# tick-shield-mk-1.net
KiCad netlist of a schematic drawn in EAGLE
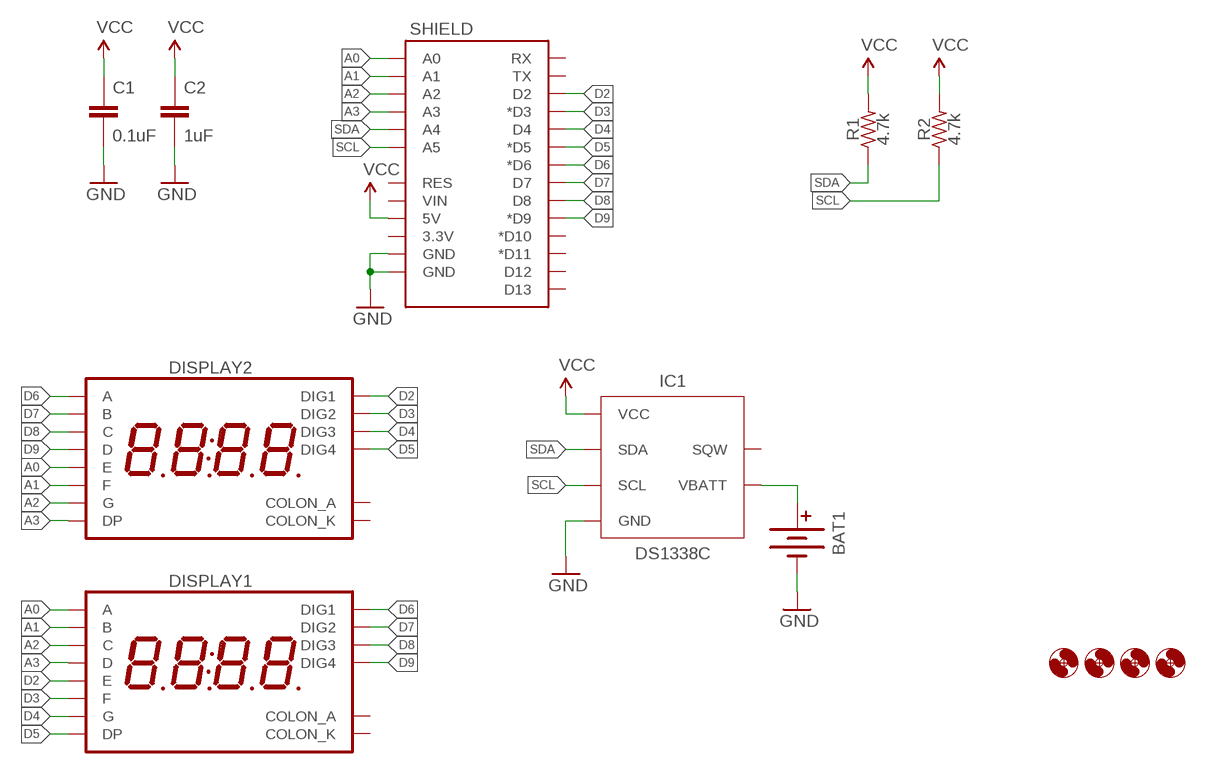
[diagram p0: schematic, sheet 1]

(export (version "E")
  (design (tool "Eeschema 10.0.6"))
  (components
    (comp (ref "BAT1")
      (value "BATTERY12MM")
      (footprint "eagle-import:BATTCON_12MM")
      (libsource (lib "eagle-import") (part "BATTERY12MM"))
    )
    (comp (ref "C1")
      (value "0.1uF")
      (footprint "eagle-import:C0603")
      (libsource (lib "eagle-import") (part "CAPACITOR-CERAMICC0603"))
    )
    (comp (ref "C2")
      (value "1uF")
      (footprint "eagle-import:C0805")
      (libsource (lib "eagle-import") (part "CAPACITOR-CERAMICC0805"))
    )
    (comp (ref "DISPLAY1")
      (value "7SEG_4DIGIT_COLON14.2MM-CC")
      (footprint "eagle-import:7SEG_4DIG_0.56IN_14MM_ADAFRUIT")
      (libsource (lib "eagle-import") (part "7SEG_4DIGIT_COLON14.2MM-CC"))
    )
    (comp (ref "DISPLAY2")
      (value "7SEG_4DIGIT_COLON14.2MM-CC")
      (footprint "eagle-import:7SEG_4DIG_0.56IN_14MM_ADAFRUIT")
      (libsource (lib "eagle-import") (part "7SEG_4DIGIT_COLON14.2MM-CC"))
    )
    (comp (ref "H1")
      (value "HOLE#2")
      (footprint "eagle-import:HOLE-#2")
      (libsource (lib "eagle-import") (part "HOLE#2"))
    )
    (comp (ref "H2")
      (value "HOLE#2")
      (footprint "eagle-import:HOLE-#2")
      (libsource (lib "eagle-import") (part "HOLE#2"))
    )
    (comp (ref "H3")
      (value "HOLE#2")
      (footprint "eagle-import:HOLE-#2")
      (libsource (lib "eagle-import") (part "HOLE#2"))
    )
    (comp (ref "H4")
      (value "HOLE#2")
      (footprint "eagle-import:HOLE-#2")
      (libsource (lib "eagle-import") (part "HOLE#2"))
    )
    (comp (ref "IC1")
      (value "DS1338C")
      (footprint "eagle-import:SO16W")
      (libsource (lib "eagle-import") (part "DS1338CSOIC16W"))
    )
    (comp (ref "R1")
      (value "4.7k")
      (footprint "eagle-import:R0603")
      (libsource (lib "eagle-import") (part "RESISTORR0603"))
    )
    (comp (ref "R2")
      (value "4.7k")
      (footprint "eagle-import:R0603")
      (libsource (lib "eagle-import") (part "RESISTORR0603"))
    )
    (comp (ref "SHIELD")
      (value "ARDUINO_SHIELD_SMALLER")
      (footprint "eagle-import:ARDUINO_SHIELD_NOOUTLINE_INSIDE_SMALLER")
      (libsource (lib "eagle-import") (part "ARDUINO_SHIELD_SMALLER"))
    )
  )
  (nets
    (net (code "1") (name "A0") (class "Default")
      (node (ref "DISPLAY1") (pin "P$13") (pinfunction "A_P$13") (pintype "passive"))
      (node (ref "DISPLAY2") (pin "P$1") (pinfunction "E_P$1") (pintype "passive"))
      (node (ref "SHIELD") (pin "A0") (pinfunction "A0_A0") (pintype "bidirectional"))
    )
    (net (code "2") (name "A1") (class "Default")
      (node (ref "DISPLAY1") (pin "P$9") (pinfunction "B_P$9") (pintype "passive"))
      (node (ref "DISPLAY2") (pin "P$12") (pinfunction "F_P$12") (pintype "passive"))
      (node (ref "SHIELD") (pin "A1") (pinfunction "A1_A1") (pintype "bidirectional"))
    )
    (net (code "3") (name "A2") (class "Default")
      (node (ref "DISPLAY1") (pin "P$4") (pinfunction "C_P$4") (pintype "passive"))
      (node (ref "DISPLAY2") (pin "P$5") (pinfunction "G_P$5") (pintype "passive"))
      (node (ref "SHIELD") (pin "A2") (pinfunction "A2_A2") (pintype "bidirectional"))
    )
    (net (code "4") (name "A3") (class "Default")
      (node (ref "DISPLAY1") (pin "P$2") (pinfunction "D_P$2") (pintype "passive"))
      (node (ref "DISPLAY2") (pin "P$3") (pinfunction "DP_P$3") (pintype "passive"))
      (node (ref "SHIELD") (pin "A3") (pinfunction "A3_A3") (pintype "bidirectional"))
    )
    (net (code "5") (name "D2") (class "Default")
      (node (ref "DISPLAY1") (pin "P$1") (pinfunction "E_P$1") (pintype "passive"))
      (node (ref "DISPLAY2") (pin "P$14") (pinfunction "DIG1_P$14") (pintype "passive"))
      (node (ref "SHIELD") (pin "D2") (pinfunction "D2_D2") (pintype "bidirectional"))
    )
    (net (code "6") (name "D3") (class "Default")
      (node (ref "DISPLAY1") (pin "P$12") (pinfunction "F_P$12") (pintype "passive"))
      (node (ref "DISPLAY2") (pin "P$11") (pinfunction "DIG2_P$11") (pintype "passive"))
      (node (ref "SHIELD") (pin "D3") (pinfunction "*D3_D3") (pintype "bidirectional"))
    )
    (net (code "7") (name "D4") (class "Default")
      (node (ref "DISPLAY1") (pin "P$5") (pinfunction "G_P$5") (pintype "passive"))
      (node (ref "DISPLAY2") (pin "P$10") (pinfunction "DIG3_P$10") (pintype "passive"))
      (node (ref "SHIELD") (pin "D4") (pinfunction "D4_D4") (pintype "bidirectional"))
    )
    (net (code "8") (name "D5") (class "Default")
      (node (ref "DISPLAY1") (pin "P$3") (pinfunction "DP_P$3") (pintype "passive"))
      (node (ref "DISPLAY2") (pin "P$6") (pinfunction "DIG4_P$6") (pintype "passive"))
      (node (ref "SHIELD") (pin "D5") (pinfunction "*D5_D5") (pintype "bidirectional"))
    )
    (net (code "9") (name "D6") (class "Default")
      (node (ref "DISPLAY1") (pin "P$14") (pinfunction "DIG1_P$14") (pintype "passive"))
      (node (ref "DISPLAY2") (pin "P$13") (pinfunction "A_P$13") (pintype "passive"))
      (node (ref "SHIELD") (pin "D6") (pinfunction "*D6_D6") (pintype "bidirectional"))
    )
    (net (code "10") (name "D7") (class "Default")
      (node (ref "DISPLAY1") (pin "P$11") (pinfunction "DIG2_P$11") (pintype "passive"))
      (node (ref "DISPLAY2") (pin "P$9") (pinfunction "B_P$9") (pintype "passive"))
      (node (ref "SHIELD") (pin "D7") (pinfunction "D7_D7") (pintype "bidirectional"))
    )
    (net (code "11") (name "D8") (class "Default")
      (node (ref "DISPLAY1") (pin "P$10") (pinfunction "DIG3_P$10") (pintype "passive"))
      (node (ref "DISPLAY2") (pin "P$4") (pinfunction "C_P$4") (pintype "passive"))
      (node (ref "SHIELD") (pin "D8") (pinfunction "D8_D8") (pintype "bidirectional"))
    )
    (net (code "12") (name "D9") (class "Default")
      (node (ref "DISPLAY1") (pin "P$6") (pinfunction "DIG4_P$6") (pintype "passive"))
      (node (ref "DISPLAY2") (pin "P$2") (pinfunction "D_P$2") (pintype "passive"))
      (node (ref "SHIELD") (pin "D9") (pinfunction "*D9_D9") (pintype "bidirectional"))
    )
    (net (code "13") (name "GND") (class "Default")
      (node (ref "BAT1") (pin "GND") (pinfunction "-_GND") (pintype "power_in"))
      (node (ref "C1") (pin "2") (pinfunction "2_2") (pintype "passive"))
      (node (ref "C2") (pin "2") (pinfunction "2_2") (pintype "passive"))
      (node (ref "IC1") (pin "10") (pinfunction "GND_10") (pintype "bidirectional"))
      (node (ref "IC1") (pin "11") (pinfunction "GND_11") (pintype "bidirectional"))
      (node (ref "IC1") (pin "12") (pinfunction "GND_12") (pintype "bidirectional"))
      (node (ref "IC1") (pin "13") (pinfunction "GND_13") (pintype "bidirectional"))
      (node (ref "IC1") (pin "15") (pinfunction "GND_15") (pintype "bidirectional"))
      (node (ref "IC1") (pin "4") (pinfunction "GND_4") (pintype "bidirectional"))
      (node (ref "IC1") (pin "5") (pinfunction "GND_5") (pintype "bidirectional"))
      (node (ref "IC1") (pin "6") (pinfunction "GND_6") (pintype "bidirectional"))
      (node (ref "IC1") (pin "7") (pinfunction "GND_7") (pintype "bidirectional"))
      (node (ref "IC1") (pin "8") (pinfunction "GND_8") (pintype "bidirectional"))
      (node (ref "IC1") (pin "9") (pinfunction "GND_9") (pintype "bidirectional"))
      (node (ref "SHIELD") (pin "GND@0") (pinfunction "GND_GND@0") (pintype "bidirectional"))
      (node (ref "SHIELD") (pin "GND@1") (pinfunction "GND_GND@1") (pintype "bidirectional"))
    )
    (net (code "14") (name "Net-(BAT1-+)") (class "Default")
      (node (ref "BAT1") (pin "PWR@1") (pinfunction "+_PWR@1") (pintype "power_in"))
      (node (ref "IC1") (pin "14") (pinfunction "VBATT_14") (pintype "bidirectional"))
    )
    (net (code "15") (name "SCL") (class "Default")
      (node (ref "IC1") (pin "1") (pinfunction "SCL_1") (pintype "bidirectional"))
      (node (ref "R2") (pin "1") (pinfunction "1_1") (pintype "passive"))
      (node (ref "SHIELD") (pin "A5") (pinfunction "A5_A5") (pintype "bidirectional"))
    )
    (net (code "16") (name "SDA") (class "Default")
      (node (ref "IC1") (pin "16") (pinfunction "SDA_16") (pintype "bidirectional"))
      (node (ref "R1") (pin "1") (pinfunction "1_1") (pintype "passive"))
      (node (ref "SHIELD") (pin "A4") (pinfunction "A4_A4") (pintype "bidirectional"))
    )
    (net (code "17") (name "VCC") (class "Default")
      (node (ref "C1") (pin "1") (pinfunction "1_1") (pintype "passive"))
      (node (ref "C2") (pin "1") (pinfunction "1_1") (pintype "passive"))
      (node (ref "IC1") (pin "3") (pinfunction "VCC_3") (pintype "bidirectional"))
      (node (ref "R1") (pin "2") (pinfunction "2_2") (pintype "passive"))
      (node (ref "R2") (pin "2") (pinfunction "2_2") (pintype "passive"))
      (node (ref "SHIELD") (pin "5V") (pinfunction "5V_5V") (pintype "bidirectional"))
    )
    (net (code "18") (name "unconnected-(DISPLAY1-COLON_A-PadP$8)") (class "Default")
      (node (ref "DISPLAY1") (pin "P$8") (pinfunction "COLON_A_P$8") (pintype "passive"))
    )
    (net (code "19") (name "unconnected-(DISPLAY1-COLON_K-PadP$7)") (class "Default")
      (node (ref "DISPLAY1") (pin "P$7") (pinfunction "COLON_K_P$7") (pintype "passive"))
    )
    (net (code "20") (name "unconnected-(DISPLAY2-COLON_A-PadP$8)") (class "Default")
      (node (ref "DISPLAY2") (pin "P$8") (pinfunction "COLON_A_P$8") (pintype "passive"))
    )
    (net (code "21") (name "unconnected-(DISPLAY2-COLON_K-PadP$7)") (class "Default")
      (node (ref "DISPLAY2") (pin "P$7") (pinfunction "COLON_K_P$7") (pintype "passive"))
    )
    (net (code "22") (name "unconnected-(IC1-SQW-Pad2)") (class "Default")
      (node (ref "IC1") (pin "2") (pinfunction "SQW_2") (pintype "bidirectional"))
    )
    (net (code "23") (name "unconnected-(SHIELD-*D10-PadD10)") (class "Default")
      (node (ref "SHIELD") (pin "D10") (pinfunction "*D10_D10") (pintype "bidirectional"))
    )
    (net (code "24") (name "unconnected-(SHIELD-*D11-PadD11)") (class "Default")
      (node (ref "SHIELD") (pin "D11") (pinfunction "*D11_D11") (pintype "bidirectional"))
    )
    (net (code "25") (name "unconnected-(SHIELD-Pad3.3V)") (class "Default")
      (node (ref "SHIELD") (pin "3.3V") (pinfunction "3.3V_3.3V") (pintype "bidirectional"))
    )
    (net (code "26") (name "unconnected-(SHIELD-PadD12)") (class "Default")
      (node (ref "SHIELD") (pin "D12") (pinfunction "D12_D12") (pintype "bidirectional"))
    )
    (net (code "27") (name "unconnected-(SHIELD-PadD13)") (class "Default")
      (node (ref "SHIELD") (pin "D13") (pinfunction "D13_D13") (pintype "bidirectional"))
    )
    (net (code "28") (name "unconnected-(SHIELD-PadRES)") (class "Default")
      (node (ref "SHIELD") (pin "RES") (pinfunction "RES_RES") (pintype "bidirectional"))
    )
    (net (code "29") (name "unconnected-(SHIELD-PadRX)") (class "Default")
      (node (ref "SHIELD") (pin "RX") (pinfunction "RX_RX") (pintype "bidirectional"))
    )
    (net (code "30") (name "unconnected-(SHIELD-PadTX)") (class "Default")
      (node (ref "SHIELD") (pin "TX") (pinfunction "TX_TX") (pintype "bidirectional"))
    )
    (net (code "31") (name "unconnected-(SHIELD-PadVIN)") (class "Default")
      (node (ref "SHIELD") (pin "VIN") (pinfunction "VIN_VIN") (pintype "bidirectional"))
    )
  )
)
